# PlataMagnitometra.net
KiCad netlist of a schematic drawn in Altium Designer
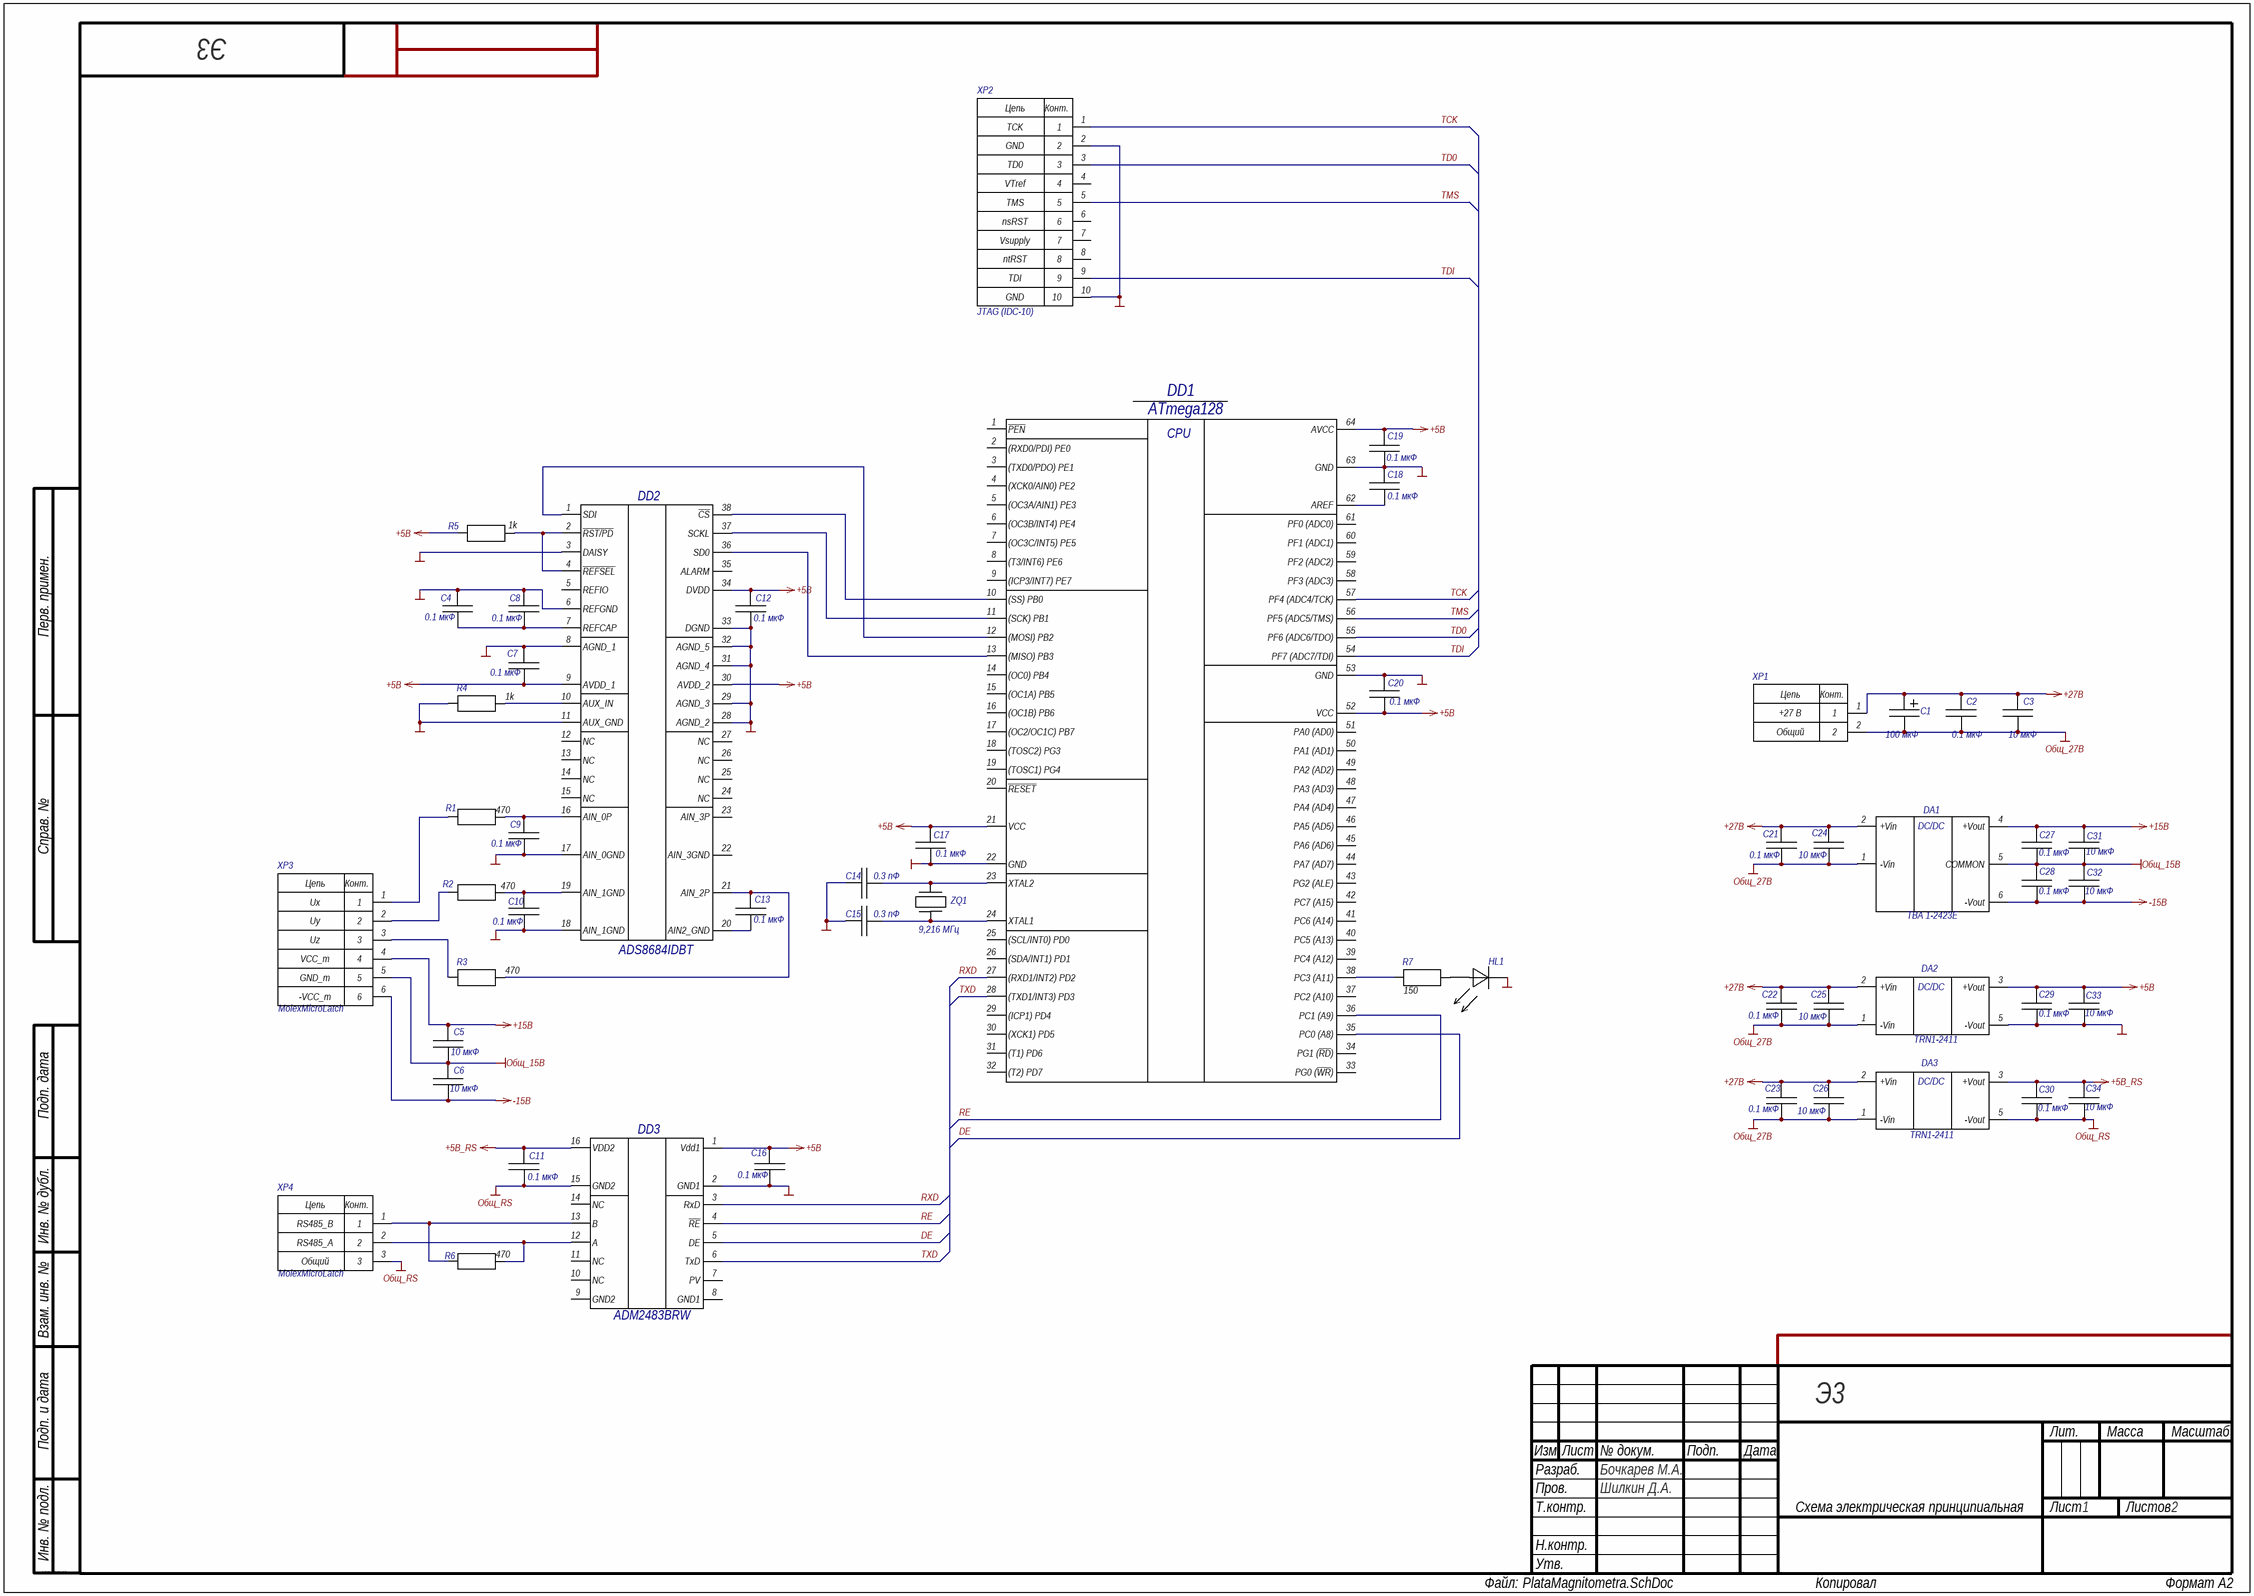
[diagram p0: PlataMagnitometra.SchDoc]

(export (version "E")
  (design (tool "Eeschema 10.0.6"))
  (components
    (comp (ref "C1")
      (value "100 мкФ")
      (footprint "TANT CAP D")
      (description "Конденсатор электролитический танталовый")
      (fields
        (field (name "MANUFACTURER") "Китай")
        (field (name "Comment") "Конденсатор электрол. 10 В 100 мкФ Ом, ±10%, TANT CAP D")
      )
      (libsource (lib "Schlib") (part "POL CAP"))
    )
    (comp (ref "C2")
      (value "0.1 мкФ")
      (footprint "CAP0805")
      (description "Конденсатор керамич. SMD")
      (fields
        (field (name "MANUFACTURER") "Murata Electronics")
        (field (name "Comment") "Конденсатор керамич. 50 В 0.1 мкФ Ом, ±10%, X7R SMD 0805")
      )
      (libsource (lib "Schlib") (part "Capacitor"))
    )
    (comp (ref "C3")
      (value "10 мкФ")
      (footprint "CAP0805")
      (description "Конденсатор керамич. SMD")
      (fields
        (field (name "MANUFACTURER") "Murata Electronics")
        (field (name "Comment") "Конденсатор керамич. 50 В 10 мкФ Ом, ±10%, X5R SMD 0805")
      )
      (libsource (lib "Schlib") (part "Capacitor"))
    )
    (comp (ref "C4")
      (value "0.1 мкФ")
      (footprint "CAP0805")
      (description "Конденсатор керамич. SMD")
      (fields
        (field (name "MANUFACTURER") "Murata Electronics")
        (field (name "Comment") "Конденсатор керамич. 50 В 0.1 мкФ Ом, ±10%, X7R SMD 0805")
      )
      (libsource (lib "Schlib") (part "Capacitor"))
    )
    (comp (ref "C5")
      (value "10 мкФ")
      (footprint "CAP0805")
      (description "Конденсатор керамич. SMD")
      (fields
        (field (name "MANUFACTURER") "Murata Electronics")
        (field (name "Comment") "Конденсатор керамич. 50 В 10 мкФ Ом, ±10%, X5R SMD 0805")
      )
      (libsource (lib "Schlib") (part "Capacitor"))
    )
    (comp (ref "C6")
      (value "10 мкФ")
      (footprint "CAP0805")
      (description "Конденсатор керамич. SMD")
      (fields
        (field (name "MANUFACTURER") "Murata Electronics")
        (field (name "Comment") "Конденсатор керамич. 50 В 10 мкФ Ом, ±10%, X5R SMD 0805")
      )
      (libsource (lib "Schlib") (part "Capacitor"))
    )
    (comp (ref "C7")
      (value "0.1 мкФ")
      (footprint "CAP0805")
      (description "Конденсатор керамич. SMD")
      (fields
        (field (name "MANUFACTURER") "Murata Electronics")
        (field (name "Comment") "Конденсатор керамич. 50 В 0.1 мкФ Ом, ±10%, X7R SMD 0805")
      )
      (libsource (lib "Schlib") (part "Capacitor"))
    )
    (comp (ref "C8")
      (value "0.1 мкФ")
      (footprint "CAP0805")
      (description "Конденсатор керамич. SMD")
      (fields
        (field (name "MANUFACTURER") "Murata Electronics")
        (field (name "Comment") "Конденсатор керамич. 50 В 0.1 мкФ Ом, ±10%, X7R SMD 0805")
      )
      (libsource (lib "Schlib") (part "Capacitor"))
    )
    (comp (ref "C9")
      (value "0.1 мкФ")
      (footprint "CAP0805")
      (description "Конденсатор керамич. SMD")
      (fields
        (field (name "MANUFACTURER") "Murata Electronics")
        (field (name "Comment") "Конденсатор керамич. 50 В 0.1 мкФ Ом, ±10%, X7R SMD 0805")
      )
      (libsource (lib "Schlib") (part "Capacitor"))
    )
    (comp (ref "C10")
      (value "0.1 мкФ")
      (footprint "CAP0805")
      (description "Конденсатор керамич. SMD")
      (fields
        (field (name "MANUFACTURER") "Murata Electronics")
        (field (name "Comment") "Конденсатор керамич. 50 В 0.1 мкФ Ом, ±10%, X7R SMD 0805")
      )
      (libsource (lib "Schlib") (part "Capacitor"))
    )
    (comp (ref "C11")
      (value "0.1 мкФ")
      (footprint "CAP0805")
      (description "Конденсатор керамич. SMD")
      (fields
        (field (name "MANUFACTURER") "Murata Electronics")
        (field (name "Comment") "Конденсатор керамич. 50 В 0.1 мкФ Ом, ±10%, X7R SMD 0805")
      )
      (libsource (lib "Schlib") (part "Capacitor"))
    )
    (comp (ref "C12")
      (value "0.1 мкФ")
      (footprint "CAP0805")
      (description "Конденсатор керамич. SMD")
      (fields
        (field (name "MANUFACTURER") "Murata Electronics")
        (field (name "Comment") "Конденсатор керамич. 50 В 0.1 мкФ Ом, ±10%, X7R SMD 0805")
      )
      (libsource (lib "Schlib") (part "Capacitor"))
    )
    (comp (ref "C13")
      (value "0.1 мкФ")
      (footprint "CAP0805")
      (description "Конденсатор керамич. SMD")
      (fields
        (field (name "MANUFACTURER") "Murata Electronics")
        (field (name "Comment") "Конденсатор керамич. 50 В 0.1 мкФ Ом, ±10%, X7R SMD 0805")
      )
      (libsource (lib "Schlib") (part "Capacitor"))
    )
    (comp (ref "C14")
      (value "0.3 пФ")
      (footprint "CAP0805")
      (description "Конденсатор керамич. SMD")
      (fields
        (field (name "MANUFACTURER") "Yageo")
        (field (name "Comment") "Конденсатор керамич. 50 В 0.3 пФ Ом, +0.25pF, X5R SMD 0805")
      )
      (libsource (lib "Schlib") (part "Capacitor"))
    )
    (comp (ref "C15")
      (value "0.3 пФ")
      (footprint "CAP0805")
      (description "Конденсатор керамич. SMD")
      (fields
        (field (name "MANUFACTURER") "Yageo")
        (field (name "Comment") "Конденсатор керамич. 50 В 0.3 пФ Ом, +0.25pF, X5R SMD 0805")
      )
      (libsource (lib "Schlib") (part "Capacitor"))
    )
    (comp (ref "C16")
      (value "0.1 мкФ")
      (footprint "CAP0805")
      (description "Конденсатор керамич. SMD")
      (fields
        (field (name "MANUFACTURER") "Murata Electronics")
        (field (name "Comment") "Конденсатор керамич. 50 В 0.1 мкФ Ом, ±10%, X7R SMD 0805")
      )
      (libsource (lib "Schlib") (part "Capacitor"))
    )
    (comp (ref "C17")
      (value "0.1 мкФ")
      (footprint "CAP0805")
      (description "Конденсатор керамич. SMD")
      (fields
        (field (name "MANUFACTURER") "Murata Electronics")
        (field (name "Comment") "Конденсатор керамич. 50 В 0.1 мкФ Ом, ±10%, X7R SMD 0805")
      )
      (libsource (lib "Schlib") (part "Capacitor"))
    )
    (comp (ref "C18")
      (value "0.1 мкФ")
      (footprint "CAP0805")
      (description "Конденсатор керамич. SMD")
      (fields
        (field (name "MANUFACTURER") "Murata Electronics")
        (field (name "Comment") "Конденсатор керамич. 50 В 0.1 мкФ Ом, ±10%, X7R SMD 0805")
      )
      (libsource (lib "Schlib") (part "Capacitor"))
    )
    (comp (ref "C19")
      (value "0.1 мкФ")
      (footprint "CAP0805")
      (description "Конденсатор керамич. SMD")
      (fields
        (field (name "MANUFACTURER") "Murata Electronics")
        (field (name "Comment") "Конденсатор керамич. 50 В 0.1 мкФ Ом, ±10%, X7R SMD 0805")
      )
      (libsource (lib "Schlib") (part "Capacitor"))
    )
    (comp (ref "C20")
      (value "0.1 мкФ")
      (footprint "CAP0805")
      (description "Конденсатор керамич. SMD")
      (fields
        (field (name "MANUFACTURER") "Murata Electronics")
        (field (name "Comment") "Конденсатор керамич. 50 В 0.1 мкФ Ом, ±10%, X7R SMD 0805")
      )
      (libsource (lib "Schlib") (part "Capacitor"))
    )
    (comp (ref "C21")
      (value "0.1 мкФ")
      (footprint "CAP0805")
      (description "Конденсатор керамич. SMD")
      (fields
        (field (name "MANUFACTURER") "Murata Electronics")
        (field (name "Comment") "Конденсатор керамич. 50 В 0.1 мкФ Ом, ±10%, X7R SMD 0805")
      )
      (libsource (lib "Schlib") (part "Capacitor"))
    )
    (comp (ref "C22")
      (value "0.1 мкФ")
      (footprint "CAP0805")
      (description "Конденсатор керамич. SMD")
      (fields
        (field (name "MANUFACTURER") "Murata Electronics")
        (field (name "Comment") "Конденсатор керамич. 50 В 0.1 мкФ Ом, ±10%, X7R SMD 0805")
      )
      (libsource (lib "Schlib") (part "Capacitor"))
    )
    (comp (ref "C23")
      (value "0.1 мкФ")
      (footprint "CAP0805")
      (description "Конденсатор керамич. SMD")
      (fields
        (field (name "MANUFACTURER") "Murata Electronics")
        (field (name "Comment") "Конденсатор керамич. 50 В 0.1 мкФ Ом, ±10%, X7R SMD 0805")
      )
      (libsource (lib "Schlib") (part "Capacitor"))
    )
    (comp (ref "C24")
      (value "10 мкФ")
      (footprint "CAP0805")
      (description "Конденсатор керамич. SMD")
      (fields
        (field (name "MANUFACTURER") "Murata Electronics")
        (field (name "Comment") "Конденсатор керамич. 50 В 10 мкФ Ом, ±10%, X5R SMD 0805")
      )
      (libsource (lib "Schlib") (part "Capacitor"))
    )
    (comp (ref "C25")
      (value "10 мкФ")
      (footprint "CAP0805")
      (description "Конденсатор керамич. SMD")
      (fields
        (field (name "MANUFACTURER") "Murata Electronics")
        (field (name "Comment") "Конденсатор керамич. 50 В 10 мкФ Ом, ±10%, X5R SMD 0805")
      )
      (libsource (lib "Schlib") (part "Capacitor"))
    )
    (comp (ref "C26")
      (value "10 мкФ")
      (footprint "CAP0805")
      (description "Конденсатор керамич. SMD")
      (fields
        (field (name "MANUFACTURER") "Murata Electronics")
        (field (name "Comment") "Конденсатор керамич. 50 В 10 мкФ Ом, ±10%, X5R SMD 0805")
      )
      (libsource (lib "Schlib") (part "Capacitor"))
    )
    (comp (ref "C27")
      (value "0.1 мкФ")
      (footprint "CAP0805")
      (description "Конденсатор керамич. SMD")
      (fields
        (field (name "MANUFACTURER") "Murata Electronics")
        (field (name "Comment") "Конденсатор керамич. 50 В 0.1 мкФ Ом, ±10%, X7R SMD 0805")
      )
      (libsource (lib "Schlib") (part "Capacitor"))
    )
    (comp (ref "C28")
      (value "0.1 мкФ")
      (footprint "CAP0805")
      (description "Конденсатор керамич. SMD")
      (fields
        (field (name "MANUFACTURER") "Murata Electronics")
        (field (name "Comment") "Конденсатор керамич. 50 В 0.1 мкФ Ом, ±10%, X7R SMD 0805")
      )
      (libsource (lib "Schlib") (part "Capacitor"))
    )
    (comp (ref "C29")
      (value "0.1 мкФ")
      (footprint "CAP0805")
      (description "Конденсатор керамич. SMD")
      (fields
        (field (name "MANUFACTURER") "Murata Electronics")
        (field (name "Comment") "Конденсатор керамич. 50 В 0.1 мкФ Ом, ±10%, X7R SMD 0805")
      )
      (libsource (lib "Schlib") (part "Capacitor"))
    )
    (comp (ref "C30")
      (value "0.1 мкФ")
      (footprint "CAP0805")
      (description "Конденсатор керамич. SMD")
      (fields
        (field (name "MANUFACTURER") "Murata Electronics")
        (field (name "Comment") "Конденсатор керамич. 50 В 0.1 мкФ Ом, ±10%, X7R SMD 0805")
      )
      (libsource (lib "Schlib") (part "Capacitor"))
    )
    (comp (ref "C31")
      (value "10 мкФ")
      (footprint "CAP0805")
      (description "Конденсатор керамич. SMD")
      (fields
        (field (name "MANUFACTURER") "Murata Electronics")
        (field (name "Comment") "Конденсатор керамич. 50 В 10 мкФ Ом, ±10%, X5R SMD 0805")
      )
      (libsource (lib "Schlib") (part "Capacitor"))
    )
    (comp (ref "C32")
      (value "10 мкФ")
      (footprint "CAP0805")
      (description "Конденсатор керамич. SMD")
      (fields
        (field (name "MANUFACTURER") "Murata Electronics")
        (field (name "Comment") "Конденсатор керамич. 50 В 10 мкФ Ом, ±10%, X5R SMD 0805")
      )
      (libsource (lib "Schlib") (part "Capacitor"))
    )
    (comp (ref "C33")
      (value "10 мкФ")
      (footprint "CAP0805")
      (description "Конденсатор керамич. SMD")
      (fields
        (field (name "MANUFACTURER") "Murata Electronics")
        (field (name "Comment") "Конденсатор керамич. 50 В 10 мкФ Ом, ±10%, X5R SMD 0805")
      )
      (libsource (lib "Schlib") (part "Capacitor"))
    )
    (comp (ref "C34")
      (value "10 мкФ")
      (footprint "CAP0805")
      (description "Конденсатор керамич. SMD")
      (fields
        (field (name "MANUFACTURER") "Murata Electronics")
        (field (name "Comment") "Конденсатор керамич. 50 В 10 мкФ Ом, ±10%, X5R SMD 0805")
      )
      (libsource (lib "Schlib") (part "Capacitor"))
    )
    (comp (ref "DA1")
      (value "DC/DC, 15Вт, Uвх: 18-36В, Uвых: 15ВDC, Iвых: 500мА")
      (footprint "TBA12411E")
      (description "DC/DC, 15Вт, Uвх: 18-36В, Uвых: 15ВDC, Iвых: 33мА")
      (fields (field (name "MANUFACTURER") "TracoPower") (field (name "MODEL") "TBA 1-2423E"))
      (libsource (lib "Schlib") (part "TBA 1 - double"))
    )
    (comp (ref "DA2")
      (value "DC/DC 1Вт, Uвх 18-36В, 5ВDC, Iвых 200мА")
      (footprint "TRN1")
      (fields (field (name "MANUFACTURER") "TracoPower") (field (name "MODEL") "TRN1-2411"))
      (libsource (lib "Schlib") (part "TRN 1 - single"))
    )
    (comp (ref "DA3")
      (value "DC/DC 1Вт, Uвх 18-36В, 5ВDC, Iвых 200мА")
      (footprint "TRN1")
      (fields (field (name "MANUFACTURER") "TracoPower") (field (name "MODEL") "TRN1-2411"))
      (libsource (lib "Schlib") (part "TRN 1 - single"))
    )
    (comp (ref "DD1")
      (value "ATmega128")
      (footprint "TQFP64")
      (description "ATMEGA128")
      (fields (field (name "MANUFACTURER") "Microchip Technology"))
      (libsource (lib "Schlib") (part "ATmega128"))
    )
    (comp (ref "DD2")
      (value "ADS8684IDBT")
      (footprint "38TSSOP")
      (fields (field (name "MANUFACTURER") "Texas Instruments"))
      (libsource (lib "Schlib") (part "ADS8684IDBT"))
    )
    (comp (ref "DD3")
      (value "ADM2483BRW")
      (footprint "SOIC-16 WIDE")
      (description "ADM2483")
      (fields (field (name "MANUFACTURER") "AnalogDevices") (field (name "MODEL") "ADM2483BRW"))
      (libsource (lib "Schlib") (part "ADM2483"))
    )
    (comp (ref "HL1")
      (value "Светодиод SMD KP-2012")
      (footprint "LED0805 Red")
      (description "Светодиод")
      (libsource (lib "Schlib") (part "LED"))
    )
    (comp (ref "R1")
      (value "470")
      (footprint "RES0805")
      (description "SMD resistor")
      (fields
        (field (name "MANUFACTURER") "Тайвань")
        (field (name "Comment") "Чип резистор 0.125Вт 470 Ом, 5%,  SMD SMD 0805")
      )
      (libsource (lib "Schlib") (part "Resistor"))
    )
    (comp (ref "R2")
      (value "470")
      (footprint "RES0805")
      (description "SMD resistor")
      (fields
        (field (name "MANUFACTURER") "Тайвань")
        (field (name "Comment") "Чип резистор 0.125Вт 470 Ом, 5%,  SMD SMD 0805")
      )
      (libsource (lib "Schlib") (part "Resistor"))
    )
    (comp (ref "R3")
      (value "470")
      (footprint "RES0805")
      (description "SMD resistor")
      (fields
        (field (name "MANUFACTURER") "Тайвань")
        (field (name "Comment") "Чип резистор 0.125Вт 470 Ом, 5%,  SMD SMD 0805")
      )
      (libsource (lib "Schlib") (part "Resistor"))
    )
    (comp (ref "R4")
      (value "1k")
      (footprint "RES0805")
      (description "SMD resistor")
      (fields
        (field (name "MANUFACTURER") "Panasonic")
        (field (name "Comment") "Чип резистор 0.125Вт 1k Ом, 5%,  SMD SMD 0805")
      )
      (libsource (lib "Schlib") (part "Resistor"))
    )
    (comp (ref "R5")
      (value "1k")
      (footprint "RES0805")
      (description "SMD resistor")
      (fields
        (field (name "MANUFACTURER") "Panasonic")
        (field (name "Comment") "Чип резистор 0.125Вт 1k Ом, 5%,  SMD SMD 0805")
      )
      (libsource (lib "Schlib") (part "Resistor"))
    )
    (comp (ref "R6")
      (value "470")
      (footprint "RES0805")
      (description "SMD resistor")
      (fields
        (field (name "MANUFACTURER") "Тайвань")
        (field (name "Comment") "Чип резистор 0.125Вт 470 Ом, 5%,  SMD SMD 0805")
      )
      (libsource (lib "Schlib") (part "Resistor"))
    )
    (comp (ref "R7")
      (value "150")
      (footprint "RES0805")
      (description "SMD resistor")
      (fields
        (field (name "MANUFACTURER") "Тайвань")
        (field (name "Comment") "Чип резистор 0.125Вт 150 Ом, 5%,  SMD SMD 0805")
      )
      (libsource (lib "Schlib") (part "Resistor"))
    )
    (comp (ref "XP1")
      (value "Коннектор JST Corporation, 2 мм, 1 ряд, 2 контактa")
      (footprint "2pinMicroLatch")
      (description "B2B-EH-A (LF)")
      (libsource (lib "Schlib") (part "2PinConn"))
    )
    (comp (ref "XP2")
      (value "JTAG (IDC-10)")
      (footprint "IDC10")
      (description "10PinConnector")
      (libsource (lib "Schlib") (part "10PinConn"))
    )
    (comp (ref "XP3")
      (value "MolexMicroLatch")
      (footprint "6pinMicroLatch")
      (description "Коннектор Micro-Latch, Signal, 2 мм, 1 ряд, 6 контактов")
      (libsource (lib "Schlib") (part "6PinConn"))
    )
    (comp (ref "XP4")
      (value "MolexMicroLatch")
      (footprint "3pinMicroLatch")
      (description "Коннектор Micro-Latch, Signal, 2 мм, 1 ряд, 3 контактa")
      (libsource (lib "Schlib") (part "3PinConn"))
    )
    (comp (ref "ZQ1")
      (value "9,216 МГц")
      (footprint "HC49S4HSMD")
      (description "Кварцевый резонатор")
      (fields
        (field (name "MANUFACTURER") "ATMEGA128-16AU")
        (field (name "Comment") "Резонатор кварцевый низкопрофильный 9.216 МГц SMT")
      )
      (libsource (lib "Schlib") (part "Quartz_resonator"))
    )
  )
  (nets
    (net (code "1") (name "+5В") (class "Default")
      (node (ref "C12") (pin "2") (pinfunction "2_2") (pintype "passive"))
      (node (ref "C16") (pin "1") (pinfunction "1_1") (pintype "passive"))
      (node (ref "C17") (pin "2") (pinfunction "2_2") (pintype "passive"))
      (node (ref "C19") (pin "1") (pinfunction "1_1") (pintype "passive"))
      (node (ref "C20") (pin "2") (pinfunction "2_2") (pintype "passive"))
      (node (ref "C29") (pin "1") (pinfunction "1_1") (pintype "passive"))
      (node (ref "C33") (pin "1") (pinfunction "1_1") (pintype "passive"))
      (node (ref "C7") (pin "1") (pinfunction "1_1") (pintype "passive"))
      (node (ref "DA2") (pin "3") (pinfunction "+Vout_3") (pintype "passive"))
      (node (ref "DD1") (pin "21") (pinfunction "VCC_21") (pintype "passive"))
      (node (ref "DD1") (pin "52") (pinfunction "VCC_52") (pintype "passive"))
      (node (ref "DD1") (pin "64") (pinfunction "AVCC_64") (pintype "passive"))
      (node (ref "DD2") (pin "30") (pinfunction "AVDD_2_30") (pintype "passive"))
      (node (ref "DD2") (pin "34") (pinfunction "DVDD_34") (pintype "passive"))
      (node (ref "DD2") (pin "9") (pinfunction "AVDD_1_9") (pintype "passive"))
      (node (ref "DD3") (pin "1") (pinfunction "Vdd1_1") (pintype "passive"))
      (node (ref "R5") (pin "2") (pinfunction "2_2") (pintype "passive"))
    )
    (net (code "2") (name "+5В_RS") (class "Default")
      (node (ref "C11") (pin "2") (pinfunction "2_2") (pintype "passive"))
      (node (ref "C30") (pin "1") (pinfunction "1_1") (pintype "passive"))
      (node (ref "C34") (pin "1") (pinfunction "1_1") (pintype "passive"))
      (node (ref "DA3") (pin "3") (pinfunction "+Vout_3") (pintype "passive"))
      (node (ref "DD3") (pin "16") (pinfunction "VDD2_16") (pintype "passive"))
    )
    (net (code "3") (name "+15В") (class "Default")
      (node (ref "C27") (pin "1") (pinfunction "1_1") (pintype "passive"))
      (node (ref "C31") (pin "1") (pinfunction "1_1") (pintype "passive"))
      (node (ref "C5") (pin "1") (pinfunction "1_1") (pintype "passive"))
      (node (ref "DA1") (pin "4") (pinfunction "+Vout_4") (pintype "passive"))
      (node (ref "XP3") (pin "4") (pinfunction "4_4") (pintype "passive"))
    )
    (net (code "4") (name "+27В") (class "Default")
      (node (ref "C1") (pin "2") (pinfunction "2_2") (pintype "passive"))
      (node (ref "C2") (pin "1") (pinfunction "1_1") (pintype "passive"))
      (node (ref "C21") (pin "1") (pinfunction "1_1") (pintype "passive"))
      (node (ref "C22") (pin "1") (pinfunction "1_1") (pintype "passive"))
      (node (ref "C23") (pin "1") (pinfunction "1_1") (pintype "passive"))
      (node (ref "C24") (pin "1") (pinfunction "1_1") (pintype "passive"))
      (node (ref "C25") (pin "1") (pinfunction "1_1") (pintype "passive"))
      (node (ref "C26") (pin "1") (pinfunction "1_1") (pintype "passive"))
      (node (ref "C3") (pin "1") (pinfunction "1_1") (pintype "passive"))
      (node (ref "DA1") (pin "2") (pinfunction "+Vin_2") (pintype "passive"))
      (node (ref "DA2") (pin "2") (pinfunction "+Vin_2") (pintype "passive"))
      (node (ref "DA3") (pin "2") (pinfunction "+Vin_2") (pintype "passive"))
      (node (ref "XP1") (pin "1") (pinfunction "1_1") (pintype "passive"))
    )
    (net (code "5") (name "-15В") (class "Default")
      (node (ref "C28") (pin "2") (pinfunction "2_2") (pintype "passive"))
      (node (ref "C32") (pin "2") (pinfunction "2_2") (pintype "passive"))
      (node (ref "C6") (pin "2") (pinfunction "2_2") (pintype "passive"))
      (node (ref "DA1") (pin "6") (pinfunction "-Vout_6") (pintype "passive"))
      (node (ref "XP3") (pin "6") (pinfunction "6_6") (pintype "passive"))
    )
    (net (code "6") (name "/DE") (class "Default")
      (node (ref "DD1") (pin "35") (pinfunction "PC0_(A8)_35") (pintype "passive"))
      (node (ref "DD3") (pin "5") (pinfunction "DE_5") (pintype "passive"))
    )
    (net (code "7") (name "/RE") (class "Default")
      (node (ref "DD1") (pin "36") (pinfunction "PC1_(A9)_36") (pintype "passive"))
      (node (ref "DD3") (pin "4") (pinfunction "~{RE}_4") (pintype "passive"))
    )
    (net (code "8") (name "/RXD") (class "Default")
      (node (ref "DD1") (pin "27") (pinfunction "(RXD1/INT2)_PD2_27") (pintype "passive"))
      (node (ref "DD3") (pin "3") (pinfunction "RxD_3") (pintype "passive"))
    )
    (net (code "9") (name "/TCK") (class "Default")
      (node (ref "DD1") (pin "57") (pinfunction "PF4_(ADC4/TCK)_57") (pintype "passive"))
      (node (ref "XP2") (pin "1") (pinfunction "1_1") (pintype "passive"))
    )
    (net (code "10") (name "/TD0") (class "Default")
      (node (ref "DD1") (pin "55") (pinfunction "PF6_(ADC6/TDO)_55") (pintype "passive"))
      (node (ref "XP2") (pin "3") (pinfunction "3_3") (pintype "passive"))
    )
    (net (code "11") (name "/TDI") (class "Default")
      (node (ref "DD1") (pin "54") (pinfunction "PF7_(ADC7/TDI)_54") (pintype "passive"))
      (node (ref "XP2") (pin "9") (pinfunction "9_9") (pintype "passive"))
    )
    (net (code "12") (name "/TMS") (class "Default")
      (node (ref "DD1") (pin "56") (pinfunction "PF5_(ADC5/TMS)_56") (pintype "passive"))
      (node (ref "XP2") (pin "5") (pinfunction "5_5") (pintype "passive"))
    )
    (net (code "13") (name "/TXD") (class "Default")
      (node (ref "DD1") (pin "28") (pinfunction "(TXD1/INT3)_PD3_28") (pintype "passive"))
      (node (ref "DD3") (pin "6") (pinfunction "TxD_6") (pintype "passive"))
    )
    (net (code "14") (name "Net-(C10-Pad2)") (class "Default")
      (node (ref "C10") (pin "2") (pinfunction "2_2") (pintype "passive"))
      (node (ref "DD2") (pin "19") (pinfunction "AIN_1GND_19") (pintype "passive"))
      (node (ref "R2") (pin "1") (pinfunction "1_1") (pintype "passive"))
    )
    (net (code "15") (name "Net-(DD1-(MISO)_PB3)") (class "Default")
      (node (ref "DD1") (pin "13") (pinfunction "(MISO)_PB3_13") (pintype "passive"))
      (node (ref "DD2") (pin "36") (pinfunction "SD0_36") (pintype "passive"))
    )
    (net (code "16") (name "Net-(DD1-(MOSI)_PB2)") (class "Default")
      (node (ref "DD1") (pin "12") (pinfunction "(MOSI)_PB2_12") (pintype "passive"))
      (node (ref "DD2") (pin "1") (pinfunction "SDI_1") (pintype "passive"))
    )
    (net (code "17") (name "Net-(DD1-(SCK)_PB1)") (class "Default")
      (node (ref "DD1") (pin "11") (pinfunction "(SCK)_PB1_11") (pintype "passive"))
      (node (ref "DD2") (pin "37") (pinfunction "SCKL_37") (pintype "passive"))
    )
    (net (code "18") (name "Net-(DD1-(SS)_PB0)") (class "Default")
      (node (ref "DD1") (pin "10") (pinfunction "(SS)_PB0_10") (pintype "passive"))
      (node (ref "DD2") (pin "38") (pinfunction "~{CS}_38") (pintype "passive"))
    )
    (net (code "19") (name "Net-(DD1-AREF)") (class "Default")
      (node (ref "C18") (pin "2") (pinfunction "2_2") (pintype "passive"))
      (node (ref "DD1") (pin "62") (pinfunction "AREF_62") (pintype "passive"))
    )
    (net (code "20") (name "Net-(DD1-PC3_(A11))") (class "Default")
      (node (ref "DD1") (pin "38") (pinfunction "PC3_(A11)_38") (pintype "passive"))
      (node (ref "R7") (pin "2") (pinfunction "2_2") (pintype "passive"))
    )
    (net (code "21") (name "Net-(DD1-XTAL1)") (class "Default")
      (node (ref "C15") (pin "1") (pinfunction "1_1") (pintype "passive"))
      (node (ref "DD1") (pin "24") (pinfunction "XTAL1_24") (pintype "passive"))
      (node (ref "ZQ1") (pin "1") (pinfunction "0_1") (pintype "passive"))
    )
    (net (code "22") (name "Net-(DD1-XTAL2)") (class "Default")
      (node (ref "C14") (pin "1") (pinfunction "1_1") (pintype "passive"))
      (node (ref "DD1") (pin "23") (pinfunction "XTAL2_23") (pintype "passive"))
      (node (ref "ZQ1") (pin "2") (pinfunction "1_2") (pintype "passive"))
    )
    (net (code "23") (name "Net-(DD2-AIN2_GND)") (class "Default")
      (node (ref "C13") (pin "1") (pinfunction "1_1") (pintype "passive"))
      (node (ref "DD2") (pin "20") (pinfunction "AIN2_GND_20") (pintype "passive"))
    )
    (net (code "24") (name "Net-(DD2-AIN_0P)") (class "Default")
      (node (ref "C9") (pin "2") (pinfunction "2_2") (pintype "passive"))
      (node (ref "DD2") (pin "16") (pinfunction "AIN_0P_16") (pintype "passive"))
      (node (ref "R1") (pin "1") (pinfunction "1_1") (pintype "passive"))
    )
    (net (code "25") (name "Net-(DD2-AIN_2P)") (class "Default")
      (node (ref "C13") (pin "2") (pinfunction "2_2") (pintype "passive"))
      (node (ref "DD2") (pin "21") (pinfunction "AIN_2P_21") (pintype "passive"))
      (node (ref "R3") (pin "1") (pinfunction "1_1") (pintype "passive"))
    )
    (net (code "26") (name "Net-(DD2-AUX_IN)") (class "Default")
      (node (ref "DD2") (pin "10") (pinfunction "AUX_IN_10") (pintype "passive"))
      (node (ref "R4") (pin "1") (pinfunction "1_1") (pintype "passive"))
    )
    (net (code "27") (name "Net-(DD2-REFCAP)") (class "Default")
      (node (ref "C4") (pin "1") (pinfunction "1_1") (pintype "passive"))
      (node (ref "C8") (pin "1") (pinfunction "1_1") (pintype "passive"))
      (node (ref "DD2") (pin "7") (pinfunction "REFCAP_7") (pintype "passive"))
    )
    (net (code "28") (name "Net-(DD2-~{REFSEL})") (class "Default")
      (node (ref "DD2") (pin "2") (pinfunction "~{RST/PD}_2") (pintype "passive"))
      (node (ref "DD2") (pin "4") (pinfunction "~{REFSEL}_4") (pintype "passive"))
      (node (ref "R5") (pin "1") (pinfunction "1_1") (pintype "passive"))
    )
    (net (code "29") (name "Net-(DD3-A)") (class "Default")
      (node (ref "DD3") (pin "12") (pinfunction "A_12") (pintype "passive"))
      (node (ref "R6") (pin "1") (pinfunction "1_1") (pintype "passive"))
      (node (ref "XP4") (pin "2") (pinfunction "2_2") (pintype "passive"))
    )
    (net (code "30") (name "Net-(DD3-B)") (class "Default")
      (node (ref "DD3") (pin "13") (pinfunction "B_13") (pintype "passive"))
      (node (ref "R6") (pin "2") (pinfunction "2_2") (pintype "passive"))
      (node (ref "XP4") (pin "1") (pinfunction "1_1") (pintype "passive"))
    )
    (net (code "31") (name "Net-(HL1-A)") (class "Default")
      (node (ref "HL1") (pin "2") (pinfunction "A_2") (pintype "passive"))
      (node (ref "R7") (pin "1") (pinfunction "1_1") (pintype "passive"))
    )
    (net (code "32") (name "Net-(R1-Pad2)") (class "Default")
      (node (ref "R1") (pin "2") (pinfunction "2_2") (pintype "passive"))
      (node (ref "XP3") (pin "1") (pinfunction "1_1") (pintype "passive"))
    )
    (net (code "33") (name "Net-(R2-Pad2)") (class "Default")
      (node (ref "R2") (pin "2") (pinfunction "2_2") (pintype "passive"))
      (node (ref "XP3") (pin "2") (pinfunction "2_2") (pintype "passive"))
    )
    (net (code "34") (name "Net-(R3-Pad2)") (class "Default")
      (node (ref "R3") (pin "2") (pinfunction "2_2") (pintype "passive"))
      (node (ref "XP3") (pin "3") (pinfunction "3_3") (pintype "passive"))
    )
    (net (code "35") (name "unconnected-(DD1-(ICP1)_PD4-Pad29)") (class "Default")
      (node (ref "DD1") (pin "29") (pinfunction "(ICP1)_PD4_29") (pintype "passive"))
    )
    (net (code "36") (name "unconnected-(DD1-(ICP3{slash}INT7)_PE7-Pad9)") (class "Default")
      (node (ref "DD1") (pin "9") (pinfunction "(ICP3/INT7)_PE7_9") (pintype "passive"))
    )
    (net (code "37") (name "unconnected-(DD1-(OC0)_PB4-Pad14)") (class "Default")
      (node (ref "DD1") (pin "14") (pinfunction "(OC0)_PB4_14") (pintype "passive"))
    )
    (net (code "38") (name "unconnected-(DD1-(OC1A)_PB5-Pad15)") (class "Default")
      (node (ref "DD1") (pin "15") (pinfunction "(OC1A)_PB5_15") (pintype "passive"))
    )
    (net (code "39") (name "unconnected-(DD1-(OC1B)_PB6-Pad16)") (class "Default")
      (node (ref "DD1") (pin "16") (pinfunction "(OC1B)_PB6_16") (pintype "passive"))
    )
    (net (code "40") (name "unconnected-(DD1-(OC2{slash}OC1C)_PB7-Pad17)") (class "Default")
      (node (ref "DD1") (pin "17") (pinfunction "(OC2/OC1C)_PB7_17") (pintype "passive"))
    )
    (net (code "41") (name "unconnected-(DD1-(OC3A{slash}AIN1)_PE3-Pad5)") (class "Default")
      (node (ref "DD1") (pin "5") (pinfunction "(OC3A/AIN1)_PE3_5") (pintype "passive"))
    )
    (net (code "42") (name "unconnected-(DD1-(OC3B{slash}INT4)_PE4-Pad6)") (class "Default")
      (node (ref "DD1") (pin "6") (pinfunction "(OC3B/INT4)_PE4_6") (pintype "passive"))
    )
    (net (code "43") (name "unconnected-(DD1-(OC3C{slash}INT5)_PE5-Pad7)") (class "Default")
      (node (ref "DD1") (pin "7") (pinfunction "(OC3C/INT5)_PE5_7") (pintype "passive"))
    )
    (net (code "44") (name "unconnected-(DD1-(RXD0{slash}PDI)_PE0-Pad2)") (class "Default")
      (node (ref "DD1") (pin "2") (pinfunction "(RXD0/PDI)_PE0_2") (pintype "passive"))
    )
    (net (code "45") (name "unconnected-(DD1-(SCL{slash}INT0)_PD0-Pad25)") (class "Default")
      (node (ref "DD1") (pin "25") (pinfunction "(SCL/INT0)_PD0_25") (pintype "passive"))
    )
    (net (code "46") (name "unconnected-(DD1-(SDA{slash}INT1)_PD1-Pad26)") (class "Default")
      (node (ref "DD1") (pin "26") (pinfunction "(SDA/INT1)_PD1_26") (pintype "passive"))
    )
    (net (code "47") (name "unconnected-(DD1-(T1)_PD6-Pad31)") (class "Default")
      (node (ref "DD1") (pin "31") (pinfunction "(T1)_PD6_31") (pintype "passive"))
    )
    (net (code "48") (name "unconnected-(DD1-(T2)_PD7-Pad32)") (class "Default")
      (node (ref "DD1") (pin "32") (pinfunction "(T2)_PD7_32") (pintype "passive"))
    )
    (net (code "49") (name "unconnected-(DD1-(T3{slash}INT6)_PE6-Pad8)") (class "Default")
      (node (ref "DD1") (pin "8") (pinfunction "(T3/INT6)_PE6_8") (pintype "passive"))
    )
    (net (code "50") (name "unconnected-(DD1-(TOSC1)_PG4-Pad19)") (class "Default")
      (node (ref "DD1") (pin "19") (pinfunction "(TOSC1)_PG4_19") (pintype "passive"))
    )
    (net (code "51") (name "unconnected-(DD1-(TOSC2)_PG3-Pad18)") (class "Default")
      (node (ref "DD1") (pin "18") (pinfunction "(TOSC2)_PG3_18") (pintype "passive"))
    )
    (net (code "52") (name "unconnected-(DD1-(TXD0{slash}PDO)_PE1-Pad3)") (class "Default")
      (node (ref "DD1") (pin "3") (pinfunction "(TXD0/PDO)_PE1_3") (pintype "passive"))
    )
    (net (code "53") (name "unconnected-(DD1-(XCK0{slash}AIN0)_PE2-Pad4)") (class "Default")
      (node (ref "DD1") (pin "4") (pinfunction "(XCK0/AIN0)_PE2_4") (pintype "passive"))
    )
    (net (code "54") (name "unconnected-(DD1-(XCK1)_PD5-Pad30)") (class "Default")
      (node (ref "DD1") (pin "30") (pinfunction "(XCK1)_PD5_30") (pintype "passive"))
    )
    (net (code "55") (name "unconnected-(DD1-PA0_(AD0)-Pad51)") (class "Default")
      (node (ref "DD1") (pin "51") (pinfunction "PA0_(AD0)_51") (pintype "passive"))
    )
    (net (code "56") (name "unconnected-(DD1-PA1_(AD1)-Pad50)") (class "Default")
      (node (ref "DD1") (pin "50") (pinfunction "PA1_(AD1)_50") (pintype "passive"))
    )
    (net (code "57") (name "unconnected-(DD1-PA2_(AD2)-Pad49)") (class "Default")
      (node (ref "DD1") (pin "49") (pinfunction "PA2_(AD2)_49") (pintype "passive"))
    )
    (net (code "58") (name "unconnected-(DD1-PA3_(AD3)-Pad48)") (class "Default")
      (node (ref "DD1") (pin "48") (pinfunction "PA3_(AD3)_48") (pintype "passive"))
    )
    (net (code "59") (name "unconnected-(DD1-PA4_(AD4)-Pad47)") (class "Default")
      (node (ref "DD1") (pin "47") (pinfunction "PA4_(AD4)_47") (pintype "passive"))
    )
    (net (code "60") (name "unconnected-(DD1-PA5_(AD5)-Pad46)") (class "Default")
      (node (ref "DD1") (pin "46") (pinfunction "PA5_(AD5)_46") (pintype "passive"))
    )
    (net (code "61") (name "unconnected-(DD1-PA6_(AD6)-Pad45)") (class "Default")
      (node (ref "DD1") (pin "45") (pinfunction "PA6_(AD6)_45") (pintype "passive"))
    )
    (net (code "62") (name "unconnected-(DD1-PA7_(AD7)-Pad44)") (class "Default")
      (node (ref "DD1") (pin "44") (pinfunction "PA7_(AD7)_44") (pintype "passive"))
    )
    (net (code "63") (name "unconnected-(DD1-PC2_(A10)-Pad37)") (class "Default")
      (node (ref "DD1") (pin "37") (pinfunction "PC2_(A10)_37") (pintype "passive"))
    )
    (net (code "64") (name "unconnected-(DD1-PC4_(A12)-Pad39)") (class "Default")
      (node (ref "DD1") (pin "39") (pinfunction "PC4_(A12)_39") (pintype "passive"))
    )
    (net (code "65") (name "unconnected-(DD1-PC5_(A13)-Pad40)") (class "Default")
      (node (ref "DD1") (pin "40") (pinfunction "PC5_(A13)_40") (pintype "passive"))
    )
    (net (code "66") (name "unconnected-(DD1-PC6_(A14)-Pad41)") (class "Default")
      (node (ref "DD1") (pin "41") (pinfunction "PC6_(A14)_41") (pintype "passive"))
    )
    (net (code "67") (name "unconnected-(DD1-PC7_(A15)-Pad42)") (class "Default")
      (node (ref "DD1") (pin "42") (pinfunction "PC7_(A15)_42") (pintype "passive"))
    )
    (net (code "68") (name "unconnected-(DD1-PF0_(ADC0)-Pad61)") (class "Default")
      (node (ref "DD1") (pin "61") (pinfunction "PF0_(ADC0)_61") (pintype "passive"))
    )
    (net (code "69") (name "unconnected-(DD1-PF1_(ADC1)-Pad60)") (class "Default")
      (node (ref "DD1") (pin "60") (pinfunction "PF1_(ADC1)_60") (pintype "passive"))
    )
    (net (code "70") (name "unconnected-(DD1-PF2_(ADC2)-Pad59)") (class "Default")
      (node (ref "DD1") (pin "59") (pinfunction "PF2_(ADC2)_59") (pintype "passive"))
    )
    (net (code "71") (name "unconnected-(DD1-PF3_(ADC3)-Pad58)") (class "Default")
      (node (ref "DD1") (pin "58") (pinfunction "PF3_(ADC3)_58") (pintype "passive"))
    )
    (net (code "72") (name "unconnected-(DD1-PG0_(~{WR})-Pad33)") (class "Default")
      (node (ref "DD1") (pin "33") (pinfunction "PG0_(~{WR})_33") (pintype "passive"))
    )
    (net (code "73") (name "unconnected-(DD1-PG1_(~{RD})-Pad34)") (class "Default")
      (node (ref "DD1") (pin "34") (pinfunction "PG1_(~{RD})_34") (pintype "passive"))
    )
    (net (code "74") (name "unconnected-(DD1-PG2_(ALE)-Pad43)") (class "Default")
      (node (ref "DD1") (pin "43") (pinfunction "PG2_(ALE)_43") (pintype "passive"))
    )
    (net (code "75") (name "unconnected-(DD1-~{PEN}-Pad1)") (class "Default")
      (node (ref "DD1") (pin "1") (pinfunction "~{PEN}_1") (pintype "passive"))
    )
    (net (code "76") (name "unconnected-(DD1-~{RESET}-Pad20)") (class "Default")
      (node (ref "DD1") (pin "20") (pinfunction "~{RESET}_20") (pintype "passive"))
    )
    (net (code "77") (name "unconnected-(DD2-AIN_3GND-Pad22)") (class "Default")
      (node (ref "DD2") (pin "22") (pinfunction "AIN_3GND_22") (pintype "passive"))
    )
    (net (code "78") (name "unconnected-(DD2-AIN_3P-Pad23)") (class "Default")
      (node (ref "DD2") (pin "23") (pinfunction "AIN_3P_23") (pintype "passive"))
    )
    (net (code "79") (name "unconnected-(DD2-ALARM-Pad35)") (class "Default")
      (node (ref "DD2") (pin "35") (pinfunction "ALARM_35") (pintype "passive"))
    )
    (net (code "80") (name "unconnected-(DD2-NC-Pad12)") (class "Default")
      (node (ref "DD2") (pin "12") (pinfunction "NC_12") (pintype "passive"))
    )
    (net (code "81") (name "unconnected-(DD2-NC-Pad13)") (class "Default")
      (node (ref "DD2") (pin "13") (pinfunction "NC_13") (pintype "passive"))
    )
    (net (code "82") (name "unconnected-(DD2-NC-Pad14)") (class "Default")
      (node (ref "DD2") (pin "14") (pinfunction "NC_14") (pintype "passive"))
    )
    (net (code "83") (name "unconnected-(DD2-NC-Pad15)") (class "Default")
      (node (ref "DD2") (pin "15") (pinfunction "NC_15") (pintype "passive"))
    )
    (net (code "84") (name "unconnected-(DD2-NC-Pad24)") (class "Default")
      (node (ref "DD2") (pin "24") (pinfunction "NC_24") (pintype "passive"))
    )
    (net (code "85") (name "unconnected-(DD2-NC-Pad25)") (class "Default")
      (node (ref "DD2") (pin "25") (pinfunction "NC_25") (pintype "passive"))
    )
    (net (code "86") (name "unconnected-(DD2-NC-Pad26)") (class "Default")
      (node (ref "DD2") (pin "26") (pinfunction "NC_26") (pintype "passive"))
    )
    (net (code "87") (name "unconnected-(DD2-NC-Pad27)") (class "Default")
      (node (ref "DD2") (pin "27") (pinfunction "NC_27") (pintype "passive"))
    )
    (net (code "88") (name "unconnected-(DD2-REFIO-Pad5)") (class "Default")
      (node (ref "DD2") (pin "5") (pinfunction "REFIO_5") (pintype "passive"))
    )
    (net (code "89") (name "unconnected-(DD3-GND1-Pad8)") (class "Default")
      (node (ref "DD3") (pin "8") (pinfunction "GND1_8") (pintype "passive"))
    )
    (net (code "90") (name "unconnected-(DD3-GND2-Pad9)") (class "Default")
      (node (ref "DD3") (pin "9") (pinfunction "GND2_9") (pintype "passive"))
    )
    (net (code "91") (name "unconnected-(DD3-NC-Pad10)") (class "Default")
      (node (ref "DD3") (pin "10") (pinfunction "NC_10") (pintype "passive"))
    )
    (net (code "92") (name "unconnected-(DD3-NC-Pad11)") (class "Default")
      (node (ref "DD3") (pin "11") (pinfunction "NC_11") (pintype "passive"))
    )
    (net (code "93") (name "unconnected-(DD3-NC-Pad14)") (class "Default")
      (node (ref "DD3") (pin "14") (pinfunction "NC_14") (pintype "passive"))
    )
    (net (code "94") (name "unconnected-(DD3-PV-Pad7)") (class "Default")
      (node (ref "DD3") (pin "7") (pinfunction "PV_7") (pintype "passive"))
    )
    (net (code "95") (name "unconnected-(XP2-Pad4)") (class "Default")
      (node (ref "XP2") (pin "4") (pinfunction "4_4") (pintype "passive"))
    )
    (net (code "96") (name "unconnected-(XP2-Pad6)") (class "Default")
      (node (ref "XP2") (pin "6") (pinfunction "6_6") (pintype "passive"))
    )
    (net (code "97") (name "unconnected-(XP2-Pad7)") (class "Default")
      (node (ref "XP2") (pin "7") (pinfunction "7_7") (pintype "passive"))
    )
    (net (code "98") (name "unconnected-(XP2-Pad8)") (class "Default")
      (node (ref "XP2") (pin "8") (pinfunction "8_8") (pintype "passive"))
    )
    (net (code "99") (name "Общ_5В") (class "Default")
      (node (ref "C10") (pin "1") (pinfunction "1_1") (pintype "passive"))
      (node (ref "C12") (pin "1") (pinfunction "1_1") (pintype "passive"))
      (node (ref "C14") (pin "2") (pinfunction "2_2") (pintype "passive"))
      (node (ref "C15") (pin "2") (pinfunction "2_2") (pintype "passive"))
      (node (ref "C16") (pin "2") (pinfunction "2_2") (pintype "passive"))
      (node (ref "C17") (pin "1") (pinfunction "1_1") (pintype "passive"))
      (node (ref "C18") (pin "1") (pinfunction "1_1") (pintype "passive"))
      (node (ref "C19") (pin "2") (pinfunction "2_2") (pintype "passive"))
      (node (ref "C20") (pin "1") (pinfunction "1_1") (pintype "passive"))
      (node (ref "C29") (pin "2") (pinfunction "2_2") (pintype "passive"))
      (node (ref "C33") (pin "2") (pinfunction "2_2") (pintype "passive"))
      (node (ref "C4") (pin "2") (pinfunction "2_2") (pintype "passive"))
      (node (ref "C7") (pin "2") (pinfunction "2_2") (pintype "passive"))
      (node (ref "C8") (pin "2") (pinfunction "2_2") (pintype "passive"))
      (node (ref "C9") (pin "1") (pinfunction "1_1") (pintype "passive"))
      (node (ref "DA2") (pin "5") (pinfunction "-Vout_5") (pintype "passive"))
      (node (ref "DD1") (pin "22") (pinfunction "GND_22") (pintype "passive"))
      (node (ref "DD1") (pin "53") (pinfunction "GND_53") (pintype "passive"))
      (node (ref "DD1") (pin "63") (pinfunction "GND_63") (pintype "passive"))
      (node (ref "DD2") (pin "11") (pinfunction "AUX_GND_11") (pintype "passive"))
      (node (ref "DD2") (pin "17") (pinfunction "AIN_0GND_17") (pintype "passive"))
      (node (ref "DD2") (pin "18") (pinfunction "AIN_1GND_18") (pintype "passive"))
      (node (ref "DD2") (pin "28") (pinfunction "AGND_2_28") (pintype "passive"))
      (node (ref "DD2") (pin "29") (pinfunction "AGND_3_29") (pintype "passive"))
      (node (ref "DD2") (pin "3") (pinfunction "DAISY_3") (pintype "passive"))
      (node (ref "DD2") (pin "31") (pinfunction "AGND_4_31") (pintype "passive"))
      (node (ref "DD2") (pin "32") (pinfunction "AGND_5_32") (pintype "passive"))
      (node (ref "DD2") (pin "33") (pinfunction "DGND_33") (pintype "passive"))
      (node (ref "DD2") (pin "6") (pinfunction "REFGND_6") (pintype "passive"))
      (node (ref "DD2") (pin "8") (pinfunction "AGND_1_8") (pintype "passive"))
      (node (ref "DD3") (pin "2") (pinfunction "GND1_2") (pintype "passive"))
      (node (ref "HL1") (pin "1") (pinfunction "C_1") (pintype "passive"))
      (node (ref "R4") (pin "2") (pinfunction "2_2") (pintype "passive"))
      (node (ref "XP2") (pin "10") (pinfunction "10_10") (pintype "passive"))
      (node (ref "XP2") (pin "2") (pinfunction "2_2") (pintype "passive"))
    )
    (net (code "100") (name "Общ_15В") (class "Default")
      (node (ref "C27") (pin "2") (pinfunction "2_2") (pintype "passive"))
      (node (ref "C28") (pin "1") (pinfunction "1_1") (pintype "passive"))
      (node (ref "C31") (pin "2") (pinfunction "2_2") (pintype "passive"))
      (node (ref "C32") (pin "1") (pinfunction "1_1") (pintype "passive"))
      (node (ref "C5") (pin "2") (pinfunction "2_2") (pintype "passive"))
      (node (ref "C6") (pin "1") (pinfunction "1_1") (pintype "passive"))
      (node (ref "DA1") (pin "5") (pinfunction "COMMON_5") (pintype "passive"))
      (node (ref "XP3") (pin "5") (pinfunction "5_5") (pintype "passive"))
    )
    (net (code "101") (name "Общ_27В") (class "Default")
      (node (ref "C1") (pin "1") (pinfunction "1_1") (pintype "passive"))
      (node (ref "C2") (pin "2") (pinfunction "2_2") (pintype "passive"))
      (node (ref "C21") (pin "2") (pinfunction "2_2") (pintype "passive"))
      (node (ref "C22") (pin "2") (pinfunction "2_2") (pintype "passive"))
      (node (ref "C23") (pin "2") (pinfunction "2_2") (pintype "passive"))
      (node (ref "C24") (pin "2") (pinfunction "2_2") (pintype "passive"))
      (node (ref "C25") (pin "2") (pinfunction "2_2") (pintype "passive"))
      (node (ref "C26") (pin "2") (pinfunction "2_2") (pintype "passive"))
      (node (ref "C3") (pin "2") (pinfunction "2_2") (pintype "passive"))
      (node (ref "DA1") (pin "1") (pinfunction "-Vin_1") (pintype "passive"))
      (node (ref "DA2") (pin "1") (pinfunction "-Vin_1") (pintype "passive"))
      (node (ref "DA3") (pin "1") (pinfunction "-Vin_1") (pintype "passive"))
      (node (ref "XP1") (pin "2") (pinfunction "2_2") (pintype "passive"))
    )
    (net (code "102") (name "Общ_RS") (class "Default")
      (node (ref "C11") (pin "1") (pinfunction "1_1") (pintype "passive"))
      (node (ref "C30") (pin "2") (pinfunction "2_2") (pintype "passive"))
      (node (ref "C34") (pin "2") (pinfunction "2_2") (pintype "passive"))
      (node (ref "DA3") (pin "5") (pinfunction "-Vout_5") (pintype "passive"))
      (node (ref "DD3") (pin "15") (pinfunction "GND2_15") (pintype "passive"))
      (node (ref "XP4") (pin "3") (pinfunction "3_3") (pintype "passive"))
    )
  )
)
